# USB_To_UART_Converter.net
KiCad netlist of a schematic drawn in Altium Designer
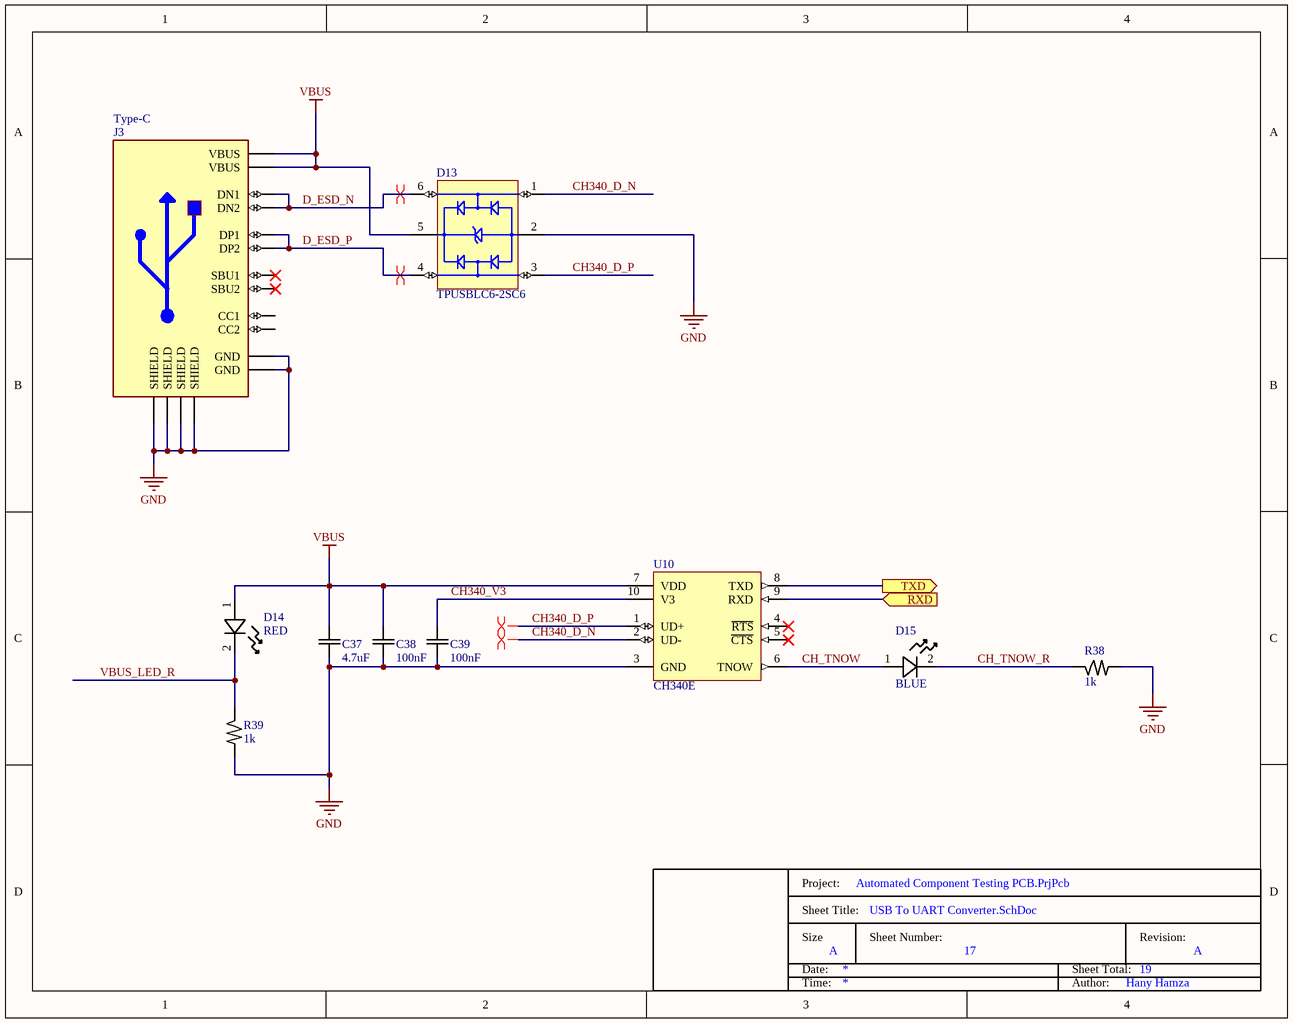
[diagram p0: USB To UART Converter.SchDoc]

(export (version "E")
  (design (tool "Eeschema 10.0.6"))
  (components
    (comp (ref "C37")
      (value "4.7uF")
      (footprint "C0603")
      (description "10V 4.7uF X7R ±10% 0603 Ceramic Capacitors ROHS")
      (fields (field (name "MF") "Chinocera") (field (name "MP") "HGC0603R7475K100NTHJ"))
      (libsource (lib "Components") (part "Cap_cer"))
    )
    (comp (ref "C38")
      (value "100nF")
      (footprint "C0603")
      (description "CAP CER 100nF 50V X7R 0603")
      (fields (field (name "MF") "HRE") (field (name "MP") "CGA0603X7R104K500JT"))
      (libsource (lib "Components") (part "Cap_cer"))
    )
    (comp (ref "C39")
      (value "100nF")
      (footprint "C0603")
      (description "CAP CER 100nF 50V X7R 0603")
      (fields (field (name "MF") "HRE") (field (name "MP") "CGA0603X7R104K500JT"))
      (libsource (lib "Components") (part "Cap_cer"))
    )
    (comp (ref "D13")
      (value "TPUSBLC6-2SC6")
      (footprint "SOT23-6")
      (description "ESD DIODE 5VWM 15VC SOT-23-6")
      (fields (field (name "MF") "TECH PUBLIC"))
      (libsource (lib "Components") (part "TPUSBLC6-2SC6"))
    )
    (comp (ref "D14")
      (value "RED")
      (footprint "LED0805 RED")
      (description "LED RED WATER CLEAR 0805 SMD")
      (fields (field (name "MF") "XINGLIGHT") (field (name "MP") "XL-TD2012SURC"))
      (libsource (lib "Components") (part "LED"))
    )
    (comp (ref "D15")
      (value "BLUE")
      (footprint "LED0805 BLUE")
      (description "20mA 500mcd~1200mcd 470nm Top-mount Blue 70mW 2.7V~3.2V 0805 LED Indication - Discrete RoHS")
      (fields (field (name "MF") "XINGLIGHT") (field (name "MP") "XL-TD2012UBC"))
      (libsource (lib "Components") (part "LED"))
    )
    (comp (ref "J3")
      (value "Type-C")
      (footprint "USB Type-C 16-Pin SMD")
      (description "CONN RCPT Type-C 16POS SMD R/A")
      (fields (field (name "MF") "DEALON") (field (name "MP") "USB-TYPE-C-019"))
      (libsource (lib "Connectors") (part "USB Type-C 16-Pin SMD"))
    )
    (comp (ref "R38")
      (value "1k")
      (footprint "R0603")
      (description "RES 1kΩ ±5% 100mW 0603")
      (fields (field (name "MF") "VO") (field (name "MP") "SCR0603J1K"))
      (libsource (lib "Components") (part "Res"))
    )
    (comp (ref "R39")
      (value "1k")
      (footprint "R0603")
      (description "RES 1kΩ ±5% 100mW 0603")
      (fields (field (name "MF") "VO") (field (name "MP") "SCR0603J1K"))
      (libsource (lib "Components") (part "Res"))
    )
    (comp (ref "U10")
      (value "CH340E")
      (footprint "MSOP-10-NO EP")
      (description "USB to Serial Port Chip CH340")
      (fields (field (name "MF") "WCH"))
      (libsource (lib "Components") (part "CH340E"))
    )
  )
  (nets
    (net (code "1") (name "/CH340_D_N") (class "Default")
      (node (ref "D13") (pin "1") (pinfunction "I/O1_1") (pintype "bidirectional"))
      (node (ref "U10") (pin "2") (pinfunction "UD-_2") (pintype "bidirectional"))
    )
    (net (code "2") (name "/CH340_D_P") (class "Default")
      (node (ref "D13") (pin "3") (pinfunction "I/O2_3") (pintype "bidirectional"))
      (node (ref "U10") (pin "1") (pinfunction "UD+_1") (pintype "bidirectional"))
    )
    (net (code "3") (name "/CH340_V3") (class "Default")
      (node (ref "C39") (pin "2") (pinfunction "2_2") (pintype "passive"))
      (node (ref "U10") (pin "10") (pinfunction "V3_10") (pintype "power_in"))
    )
    (net (code "4") (name "/CH_TNOW") (class "Default")
      (node (ref "D15") (pin "1") (pinfunction "1_1") (pintype "passive"))
      (node (ref "U10") (pin "6") (pinfunction "TNOW_6") (pintype "output"))
    )
    (net (code "5") (name "/CH_TNOW_R") (class "Default")
      (node (ref "D15") (pin "2") (pinfunction "2_2") (pintype "passive"))
      (node (ref "R38") (pin "2") (pinfunction "2_2") (pintype "passive"))
    )
    (net (code "6") (name "/D_ESD_N") (class "Default")
      (node (ref "D13") (pin "6") (pinfunction "I/O1_6") (pintype "bidirectional"))
      (node (ref "J3") (pin "A7") (pinfunction "DN1_A7") (pintype "bidirectional"))
      (node (ref "J3") (pin "B7") (pinfunction "DN2_B7") (pintype "bidirectional"))
    )
    (net (code "7") (name "/D_ESD_P") (class "Default")
      (node (ref "D13") (pin "4") (pinfunction "I/O2_4") (pintype "bidirectional"))
      (node (ref "J3") (pin "A6") (pinfunction "DP1_A6") (pintype "bidirectional"))
      (node (ref "J3") (pin "B6") (pinfunction "DP2_B6") (pintype "bidirectional"))
    )
    (net (code "8") (name "/RXD") (class "Default")
      (node (ref "U10") (pin "9") (pinfunction "RXD_9") (pintype "input"))
    )
    (net (code "9") (name "/TXD") (class "Default")
      (node (ref "U10") (pin "8") (pinfunction "TXD_8") (pintype "output"))
    )
    (net (code "10") (name "/VBUS_LED_R") (class "Default")
      (node (ref "D14") (pin "2") (pinfunction "2_2") (pintype "passive"))
      (node (ref "R39") (pin "2") (pinfunction "2_2") (pintype "passive"))
    )
    (net (code "11") (name "GND") (class "Default")
      (node (ref "C37") (pin "1") (pinfunction "1_1") (pintype "passive"))
      (node (ref "C38") (pin "1") (pinfunction "1_1") (pintype "passive"))
      (node (ref "C39") (pin "1") (pinfunction "1_1") (pintype "passive"))
      (node (ref "D13") (pin "2") (pinfunction "GND_2") (pintype "power_in"))
      (node (ref "J3") (pin "A1_B12") (pinfunction "GND_A1_B12") (pintype "power_in"))
      (node (ref "J3") (pin "B1_A12") (pinfunction "GND_B1_A12") (pintype "power_in"))
      (node (ref "J3") (pin "S1") (pinfunction "SHIELD_S1") (pintype "passive"))
      (node (ref "J3") (pin "S2") (pinfunction "SHIELD_S2") (pintype "passive"))
      (node (ref "J3") (pin "S3") (pinfunction "SHIELD_S3") (pintype "passive"))
      (node (ref "J3") (pin "S4") (pinfunction "SHIELD_S4") (pintype "passive"))
      (node (ref "R38") (pin "1") (pinfunction "1_1") (pintype "passive"))
      (node (ref "R39") (pin "1") (pinfunction "1_1") (pintype "passive"))
      (node (ref "U10") (pin "3") (pinfunction "GND_3") (pintype "power_in"))
    )
    (net (code "12") (name "VBUS") (class "Default")
      (node (ref "C37") (pin "2") (pinfunction "2_2") (pintype "passive"))
      (node (ref "C38") (pin "2") (pinfunction "2_2") (pintype "passive"))
      (node (ref "D13") (pin "5") (pinfunction "VBUS_5") (pintype "power_in"))
      (node (ref "D14") (pin "1") (pinfunction "1_1") (pintype "passive"))
      (node (ref "J3") (pin "A4_B9") (pinfunction "VBUS_A4_B9") (pintype "power_in"))
      (node (ref "J3") (pin "B4_A9") (pinfunction "VBUS_B4_A9") (pintype "power_in"))
      (node (ref "U10") (pin "7") (pinfunction "VDD_7") (pintype "power_in"))
    )
    (net (code "13") (name "unconnected-(J3-CC1-PadA5)") (class "Default")
      (node (ref "J3") (pin "A5") (pinfunction "CC1_A5") (pintype "bidirectional"))
    )
    (net (code "14") (name "unconnected-(J3-CC2-PadB5)") (class "Default")
      (node (ref "J3") (pin "B5") (pinfunction "CC2_B5") (pintype "bidirectional"))
    )
    (net (code "15") (name "unconnected-(J3-SBU1-PadA8)") (class "Default")
      (node (ref "J3") (pin "A8") (pinfunction "SBU1_A8") (pintype "bidirectional+no_connect"))
    )
    (net (code "16") (name "unconnected-(J3-SBU2-PadB8)") (class "Default")
      (node (ref "J3") (pin "B8") (pinfunction "SBU2_B8") (pintype "bidirectional+no_connect"))
    )
    (net (code "17") (name "unconnected-(U10-~{CTS}-Pad5)") (class "Default")
      (node (ref "U10") (pin "5") (pinfunction "~{CTS}_5") (pintype "input+no_connect"))
    )
    (net (code "18") (name "unconnected-(U10-~{RTS}-Pad4)") (class "Default")
      (node (ref "U10") (pin "4") (pinfunction "~{RTS}_4") (pintype "input+no_connect"))
    )
  )
)
